# Panel_Mode_Switch.net
KiCad netlist of a schematic drawn in Altium Designer
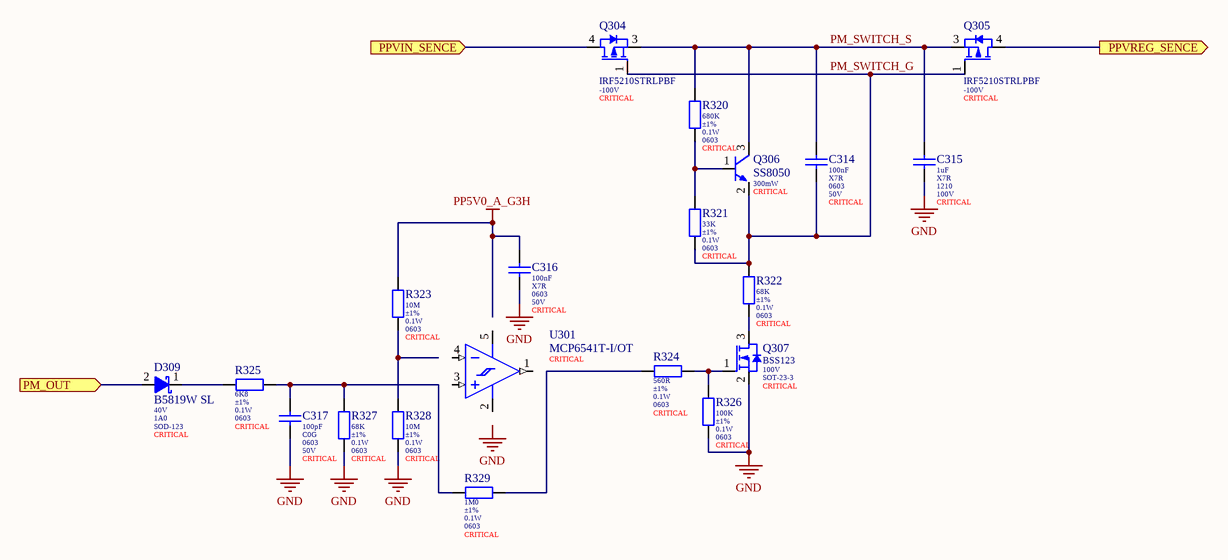
[diagram p0: Panel Mode Switch.SchDoc]

(export (version "E")
  (design (tool "Eeschema 10.0.6"))
  (components
    (comp (ref "C314")
      (value "100nF")
      (footprint "0603 (Yageo DA) B")
      (description "MLCC 100nF 50V 0603 X7R ±10%")
      (fields
        (field (name "DIELECTRIC") "X7R")
        (field (name "PACKAGE") "0603")
        (field (name "VOLTAGE") "50V")
        (field (name "POPULATE") "CRITICAL")
        (field (name "LCSC PART NUMBER") "C14663")
        (field (name "TOLERANCE") "±10%")
      )
      (libsource (lib "University of Cape Town") (part "Symbol"))
    )
    (comp (ref "C315")
      (value "1uF")
      (footprint "1212_250_J (Samsumg) B")
      (description "MLCC 1uF 1210 100V X7R ±10%")
      (fields
        (field (name "DIELECTRIC") "X7R")
        (field (name "PACKAGE") "1210")
        (field (name "VOLTAGE") "100V")
        (field (name "POPULATE") "CRITICAL")
        (field (name "MANUFACTURER") "Samsung")
        (field (name "TOLERANCE") "±10%")
      )
      (libsource (lib "University of Cape Town") (part "Symbol"))
    )
    (comp (ref "C316")
      (value "100nF")
      (footprint "0603 (Yageo DA) B")
      (description "MLCC 100nF 50V 0603 X7R ±10%")
      (fields
        (field (name "DIELECTRIC") "X7R")
        (field (name "PACKAGE") "0603")
        (field (name "VOLTAGE") "50V")
        (field (name "POPULATE") "CRITICAL")
        (field (name "LCSC PART NUMBER") "C14663")
        (field (name "TOLERANCE") "±10%")
      )
      (libsource (lib "University of Cape Town") (part "Symbol"))
    )
    (comp (ref "C317")
      (value "100pF")
      (footprint "0603_080_8 (Samsung) B")
      (description "MLCC 100pF 0603 50V C0G ±0.1pF")
      (fields
        (field (name "DIELECTRIC") "C0G")
        (field (name "PACKAGE") "0603")
        (field (name "VOLTAGE") "50V")
        (field (name "POPULATE") "CRITICAL")
        (field (name "LCSC PART NUMBER") "C14858")
        (field (name "MANUFACTURER") "Samsung")
      )
      (libsource (lib "University of Cape Town") (part "Symbol"))
    )
    (comp (ref "D309")
      (value "B5819W SL")
      (footprint "SOD-123 (JCET) B")
      (description "Schottky Barrier Diode 40V 1A 600mV SOD-123 JCET")
      (fields
        (field (name "BLOCKING VOLTAGE") "40V")
        (field (name "FORWARD CURRENT") "1A0")
        (field (name "PACKAGE") "SOD-123")
        (field (name "PLACEMENT") "CRITICAL")
        (field (name "LCSC PART NUMBER") "C8598")
      )
      (libsource (lib "University of Cape Town") (part "Schottky Diode"))
    )
    (comp (ref "Q304")
      (value "IRF5210STRLPBF")
      (footprint "D2PAC (IRF5210) B")
      (description "MOSFET P-Channel 100V 38A 3-Pin (2+Tab) D2PAK")
      (fields
        (field (name "MAXIMUM DRAIN SOURCE VOLTAGE") "-100V")
        (field (name "PLACEMENT") "CRITICAL")
        (field (name "LCSC PART NUMBER") "C2622")
      )
      (libsource (lib "University of Cape Town") (part "P Channel MOSFET TO-263"))
    )
    (comp (ref "Q305")
      (value "IRF5210STRLPBF")
      (footprint "D2PAC (IRF5210) B")
      (description "MOSFET P-Channel 100V 38A 3-Pin (2+Tab) D2PAK")
      (fields
        (field (name "MAXIMUM DRAIN SOURCE VOLTAGE") "-100V")
        (field (name "PLACEMENT") "CRITICAL")
        (field (name "LCSC PART NUMBER") "C2622")
      )
      (libsource (lib "University of Cape Town") (part "P Channel MOSFET TO-263"))
    )
    (comp (ref "Q306")
      (value "SS8050")
      (footprint "SOT-23-5 (SS8050) B")
      (description "BJT NPN 1A5 25V SOT-23-3")
      (fields
        (field (name "POWER") "300mW")
        (field (name "PLACEMENT") "CRITICAL")
        (field (name "MANUFACTURER") "Changjiang Electronics")
        (field (name "LCSC PART NUMBER") "C2150")
      )
      (libsource (lib "University of Cape Town") (part "SS8050"))
    )
    (comp (ref "Q307")
      (value "BSS123")
      (footprint "SOT-23-3 (2N7002) B")
      (description "Small Signal MOSFET, 170mA, 100V, N-Channel, Enhancement, JCET SOT-23-3")
      (fields
        (field (name "MAXIMUM DRAIN SOURCE VOLTAGE") "100V")
        (field (name "PACKAGE") "SOT-23-3")
        (field (name "PLACEMENT") "CRITICAL")
        (field (name "POWER") "0.35W")
        (field (name "MANUFACTURER") "JCET")
      )
      (libsource (lib "University of Cape Town") (part "N Channel Transistor SOT-23-3"))
    )
    (comp (ref "R320")
      (value "680K")
      (footprint "0603 (Uniroyal) B")
      (description "Resistor 680K 0603 ±1% Thick Film Uniroyal")
      (fields
        (field (name "TOLERANCE") "±1%")
        (field (name "POWER") "0.1W")
        (field (name "PACKAGE") "0603")
        (field (name "POPULATE") "CRITICAL")
        (field (name "MANUFACTURER") "Uniroyal")
        (field (name "LCSC PART NUMBER") "C25822")
      )
      (libsource (lib "University of Cape Town") (part "Chip Resistor"))
    )
    (comp (ref "R321")
      (value "33K")
      (footprint "0603 (Uniroyal) B")
      (description "Resistor 33K 0603 ±1% Thick Film Uniroyal")
      (fields
        (field (name "TOLERANCE") "±1%")
        (field (name "POWER") "0.1W")
        (field (name "PACKAGE") "0603")
        (field (name "POPULATE") "CRITICAL")
        (field (name "MANUFACTURER") "Uniroyal")
        (field (name "LCSC PART NUMBER") "C4216")
      )
      (libsource (lib "University of Cape Town") (part "Chip Resistor"))
    )
    (comp (ref "R322")
      (value "68K")
      (footprint "0603 (Uniroyal) B")
      (description "Resistor 68K 0603 ±1% Thick Film Uniroyal")
      (fields
        (field (name "TOLERANCE") "±1%")
        (field (name "POWER") "0.1W")
        (field (name "PACKAGE") "0603")
        (field (name "POPULATE") "CRITICAL")
        (field (name "MANUFACTURER") "Uniroyal")
        (field (name "LCSC PART NUMBER") "C23231")
      )
      (libsource (lib "University of Cape Town") (part "Chip Resistor"))
    )
    (comp (ref "R323")
      (value "10M")
      (footprint "0603 (Uniroyal) B")
      (description "Resistor 10M 0603 ±1% Thick Film Uniroyal")
      (fields
        (field (name "TOLERANCE") "±1%")
        (field (name "POWER") "0.1W")
        (field (name "PACKAGE") "0603")
        (field (name "POPULATE") "CRITICAL")
        (field (name "MANUFACTURER") "Uniroyal")
        (field (name "LCSC PART NUMBER") "C7250")
      )
      (libsource (lib "University of Cape Town") (part "Chip Resistor"))
    )
    (comp (ref "R324")
      (value "560R")
      (footprint "0603 (Uniroyal) B")
      (description "Resistor 560R 0603 ±1% Thick Film Uniroyal")
      (fields
        (field (name "TOLERANCE") "±1%")
        (field (name "POWER") "0.1W")
        (field (name "PACKAGE") "0603")
        (field (name "POPULATE") "CRITICAL")
        (field (name "MANUFACTURER") "Uniroyal")
        (field (name "LCSC PART NUMBER") "C23204")
      )
      (libsource (lib "University of Cape Town") (part "Chip Resistor"))
    )
    (comp (ref "R325")
      (value "6K8")
      (footprint "0603 (Uniroyal) B")
      (description "Resistor 6K8 0603 ±1% Thick Film Uniroyal")
      (fields
        (field (name "TOLERANCE") "±1%")
        (field (name "POWER") "0.1W")
        (field (name "PACKAGE") "0603")
        (field (name "POPULATE") "CRITICAL")
        (field (name "MANUFACTURER") "Uniroyal")
        (field (name "LCSC PART NUMBER") "C23212")
      )
      (libsource (lib "University of Cape Town") (part "Chip Resistor"))
    )
    (comp (ref "R326")
      (value "100K")
      (footprint "0603 (Uniroyal) B")
      (description "Resistor 100K 0603 ±1% Thick Film Uniroyal")
      (fields
        (field (name "TOLERANCE") "±1%")
        (field (name "POWER") "0.1W")
        (field (name "PACKAGE") "0603")
        (field (name "POPULATE") "CRITICAL")
        (field (name "MANUFACTURER") "Uniroyal")
        (field (name "LCSC PART NUMBER") "C25803")
      )
      (libsource (lib "University of Cape Town") (part "Chip Resistor"))
    )
    (comp (ref "R327")
      (value "68K")
      (footprint "0603 (Uniroyal) B")
      (description "Resistor 68K 0603 ±1% Thick Film Uniroyal")
      (fields
        (field (name "TOLERANCE") "±1%")
        (field (name "POWER") "0.1W")
        (field (name "PACKAGE") "0603")
        (field (name "POPULATE") "CRITICAL")
        (field (name "MANUFACTURER") "Uniroyal")
        (field (name "LCSC PART NUMBER") "C23231")
      )
      (libsource (lib "University of Cape Town") (part "Chip Resistor"))
    )
    (comp (ref "R328")
      (value "10M")
      (footprint "0603 (Uniroyal) B")
      (description "Resistor 10M 0603 ±1% Thick Film Uniroyal")
      (fields
        (field (name "TOLERANCE") "±1%")
        (field (name "POWER") "0.1W")
        (field (name "PACKAGE") "0603")
        (field (name "POPULATE") "CRITICAL")
        (field (name "MANUFACTURER") "Uniroyal")
        (field (name "LCSC PART NUMBER") "C7250")
      )
      (libsource (lib "University of Cape Town") (part "Chip Resistor"))
    )
    (comp (ref "R329")
      (value "1M0")
      (footprint "0603 (Uniroyal) B")
      (description "Resistor 1M0 0603 ±1% Thick Film Uniroyal")
      (fields
        (field (name "TOLERANCE") "±1%")
        (field (name "POWER") "0.1W")
        (field (name "PACKAGE") "0603")
        (field (name "POPULATE") "CRITICAL")
        (field (name "MANUFACTURER") "Uniroyal")
        (field (name "LCSC PART NUMBER") "C22935")
      )
      (libsource (lib "University of Cape Town") (part "Chip Resistor"))
    )
    (comp (ref "U301")
      (value "MCP6541T-I/OT")
      (footprint "SOT-23-5 (MCP75x) B")
      (description "Comparator, Push-Pull, 1V6-5V5, 600nA,  SOT-23-5")
      (fields (field (name "PLACEMENT") "CRITICAL") (field (name "LCSC PART NUMBER") "C80839"))
      (libsource (lib "University of Cape Town") (part "MCP7541"))
    )
  )
  (nets
    (net (code "1") (name "/PM_OUT") (class "Default")
      (node (ref "D309") (pin "2") (pinfunction "A_2") (pintype "passive"))
    )
    (net (code "2") (name "/PM_SWITCH_G") (class "Default")
      (node (ref "C314") (pin "2") (pinfunction "2_2") (pintype "passive"))
      (node (ref "Q304") (pin "1") (pinfunction "G_1") (pintype "passive"))
      (node (ref "Q305") (pin "1") (pinfunction "G_1") (pintype "passive"))
      (node (ref "Q306") (pin "2") (pinfunction "E_2") (pintype "passive"))
      (node (ref "R321") (pin "2") (pinfunction "2_2") (pintype "passive"))
      (node (ref "R322") (pin "1") (pinfunction "1_1") (pintype "passive"))
    )
    (net (code "3") (name "/PM_SWITCH_S") (class "Default")
      (node (ref "C314") (pin "1") (pinfunction "1_1") (pintype "passive"))
      (node (ref "C315") (pin "1") (pinfunction "1_1") (pintype "passive"))
      (node (ref "Q304") (pin "3") (pinfunction "S_3") (pintype "passive"))
      (node (ref "Q305") (pin "3") (pinfunction "S_3") (pintype "passive"))
      (node (ref "Q306") (pin "3") (pinfunction "C_3") (pintype "passive"))
      (node (ref "R320") (pin "1") (pinfunction "1_1") (pintype "passive"))
    )
    (net (code "4") (name "/PPVIN_SENCE") (class "Default")
      (node (ref "Q304") (pin "4") (pinfunction "D_4") (pintype "passive"))
    )
    (net (code "5") (name "/PPVREG_SENCE") (class "Default")
      (node (ref "Q305") (pin "4") (pinfunction "D_4") (pintype "passive"))
    )
    (net (code "6") (name "GND") (class "Default")
      (node (ref "C315") (pin "2") (pinfunction "2_2") (pintype "passive"))
      (node (ref "C316") (pin "2") (pinfunction "2_2") (pintype "passive"))
      (node (ref "C317") (pin "2") (pinfunction "2_2") (pintype "passive"))
      (node (ref "Q307") (pin "2") (pinfunction "S_2") (pintype "passive"))
      (node (ref "R326") (pin "2") (pinfunction "2_2") (pintype "passive"))
      (node (ref "R327") (pin "2") (pinfunction "2_2") (pintype "passive"))
      (node (ref "R328") (pin "2") (pinfunction "2_2") (pintype "passive"))
    )
    (net (code "7") (name "Net-(C317-Pad1)") (class "Default")
      (node (ref "C317") (pin "1") (pinfunction "1_1") (pintype "passive"))
      (node (ref "R325") (pin "1") (pinfunction "1_1") (pintype "passive"))
      (node (ref "R327") (pin "1") (pinfunction "1_1") (pintype "passive"))
      (node (ref "R329") (pin "1") (pinfunction "1_1") (pintype "passive"))
    )
    (net (code "8") (name "Net-(D309-K)") (class "Default")
      (node (ref "D309") (pin "1") (pinfunction "K_1") (pintype "passive"))
      (node (ref "R325") (pin "2") (pinfunction "2_2") (pintype "passive"))
    )
    (net (code "9") (name "Net-(Q306-B)") (class "Default")
      (node (ref "Q306") (pin "1") (pinfunction "B_1") (pintype "passive"))
      (node (ref "R320") (pin "2") (pinfunction "2_2") (pintype "passive"))
      (node (ref "R321") (pin "1") (pinfunction "1_1") (pintype "passive"))
    )
    (net (code "10") (name "Net-(Q307-D)") (class "Default")
      (node (ref "Q307") (pin "3") (pinfunction "D_3") (pintype "passive"))
      (node (ref "R322") (pin "2") (pinfunction "2_2") (pintype "passive"))
    )
    (net (code "11") (name "Net-(Q307-G)") (class "Default")
      (node (ref "Q307") (pin "1") (pinfunction "G_1") (pintype "passive"))
      (node (ref "R324") (pin "2") (pinfunction "2_2") (pintype "passive"))
      (node (ref "R326") (pin "1") (pinfunction "1_1") (pintype "passive"))
    )
    (net (code "12") (name "Net-(R323-Pad2)") (class "Default")
      (node (ref "R323") (pin "2") (pinfunction "2_2") (pintype "passive"))
      (node (ref "R328") (pin "1") (pinfunction "1_1") (pintype "passive"))
    )
    (net (code "13") (name "Net-(R324-Pad1)") (class "Default")
      (node (ref "R324") (pin "1") (pinfunction "1_1") (pintype "passive"))
      (node (ref "R329") (pin "2") (pinfunction "2_2") (pintype "passive"))
    )
    (net (code "14") (name "PP5V0_A_G3H") (class "Default")
      (node (ref "C316") (pin "1") (pinfunction "1_1") (pintype "passive"))
      (node (ref "R323") (pin "1") (pinfunction "1_1") (pintype "passive"))
    )
    (net (code "15") (name "unconnected-(U301-OUT-Pad1)") (class "Default")
      (node (ref "U301") (pin "1") (pinfunction "OUT_1") (pintype "output"))
    )
    (net (code "16") (name "unconnected-(U301-VDD-Pad5)") (class "Default")
      (node (ref "U301") (pin "5") (pinfunction "VDD_5") (pintype "power_in"))
    )
    (net (code "17") (name "unconnected-(U301-VIN+-Pad3)") (class "Default")
      (node (ref "U301") (pin "3") (pinfunction "VIN+_3") (pintype "input"))
    )
    (net (code "18") (name "unconnected-(U301-VIN--Pad4)") (class "Default")
      (node (ref "U301") (pin "4") (pinfunction "VIN-_4") (pintype "input"))
    )
    (net (code "19") (name "unconnected-(U301-VSS-Pad2)") (class "Default")
      (node (ref "U301") (pin "2") (pinfunction "VSS_2") (pintype "power_in"))
    )
  )
)
